# board.net
KiCad netlist of a schematic drawn in EAGLE
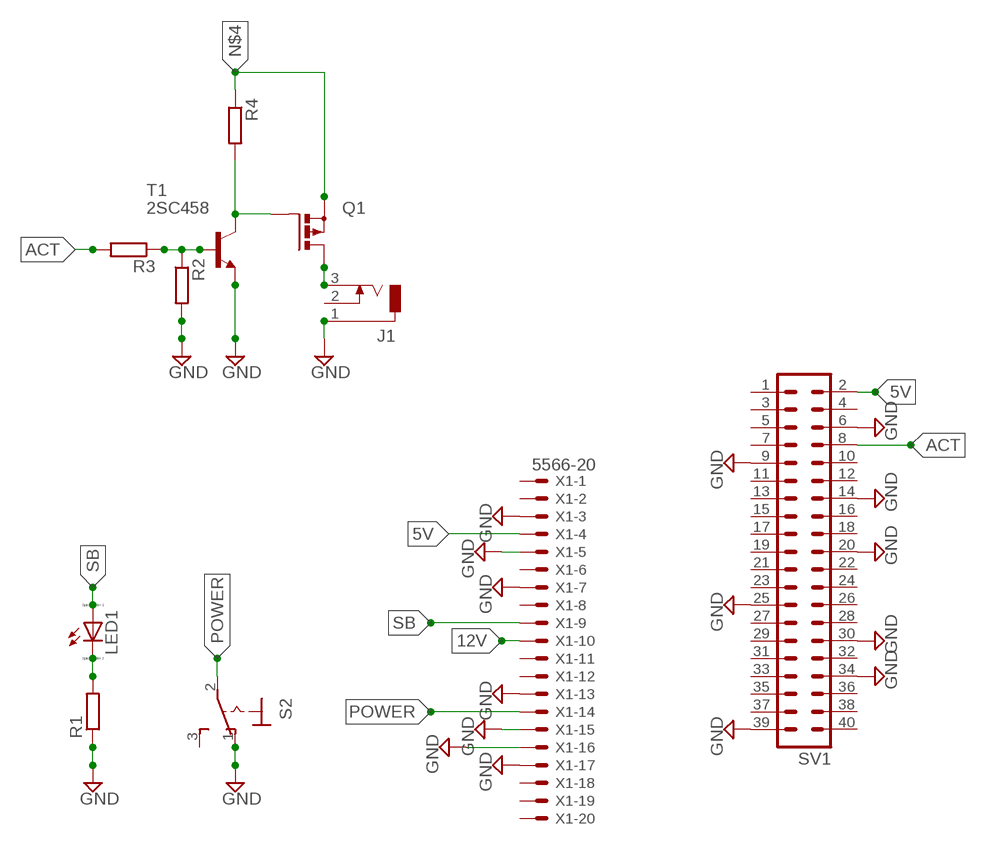
[diagram p0: schematic, sheet 1]

(export (version "E")
  (design (tool "Eeschema 10.0.6"))
  (components
    (comp (ref "J1")
      (value "DCJ0303")
      (footprint "eagle-import:DCJ0303")
      (libsource (lib "eagle-import") (part "DCJ0303"))
    )
    (comp (ref "LED1")
      (value "LED_ELD260")
      (footprint "eagle-import:LED_LD260")
      (libsource (lib "eagle-import") (part "LED_ELD260"))
    )
    (comp (ref "Q1")
      (value "PMOSFET_PTO220BV")
      (footprint "eagle-import:TO220BV")
      (libsource (lib "eagle-import") (part "PMOSFET_PTO220BV"))
    )
    (comp (ref "R1")
      (value "R-EU_0309/10")
      (footprint "eagle-import:0309_10")
      (libsource (lib "eagle-import") (part "R-EU_0309/10"))
    )
    (comp (ref "R2")
      (value "R-EU_0309/10")
      (footprint "eagle-import:0309_10")
      (libsource (lib "eagle-import") (part "R-EU_0309/10"))
    )
    (comp (ref "R3")
      (value "R-EU_0309/10")
      (footprint "eagle-import:0309_10")
      (libsource (lib "eagle-import") (part "R-EU_0309/10"))
    )
    (comp (ref "R4")
      (value "R-EU_0309/10")
      (footprint "eagle-import:0309_10")
      (libsource (lib "eagle-import") (part "R-EU_0309/10"))
    )
    (comp (ref "S2")
      (value "320-916")
      (footprint "eagle-import:320-916")
      (libsource (lib "eagle-import") (part "320-916"))
    )
    (comp (ref "SV1")
      (value "MA20-2")
      (footprint "eagle-import:MA20-2")
      (libsource (lib "eagle-import") (part "MA20-2"))
    )
    (comp (ref "T1")
      (value "2SC458")
      (footprint "eagle-import:TO92-ECB")
      (libsource (lib "eagle-import") (part "2SC458"))
    )
    (comp (ref "X1")
      (value "5566-20")
      (footprint "eagle-import:5566-20")
      (libsource (lib "eagle-import") (part "5566-20"))
    )
  )
  (nets
    (net (code "1") (name "5V") (class "Default")
      (node (ref "SV1") (pin "2") (pinfunction "2_2") (pintype "passive"))
      (node (ref "X1") (pin "4") (pinfunction "S_4") (pintype "passive"))
    )
    (net (code "2") (name "12V") (class "Default")
      (node (ref "X1") (pin "10") (pinfunction "S_10") (pintype "passive"))
    )
    (net (code "3") (name "ACT") (class "Default")
      (node (ref "R3") (pin "2") (pinfunction "2_2") (pintype "passive"))
      (node (ref "SV1") (pin "8") (pinfunction "8_8") (pintype "passive"))
    )
    (net (code "4") (name "GND") (class "Default")
      (node (ref "J1") (pin "1") (pinfunction "1_1") (pintype "passive"))
      (node (ref "R1") (pin "1") (pinfunction "1_1") (pintype "passive"))
      (node (ref "R2") (pin "2") (pinfunction "2_2") (pintype "passive"))
      (node (ref "S2") (pin "1") (pinfunction "O_1") (pintype "passive"))
      (node (ref "SV1") (pin "14") (pinfunction "14_14") (pintype "passive"))
      (node (ref "SV1") (pin "20") (pinfunction "20_20") (pintype "passive"))
      (node (ref "SV1") (pin "25") (pinfunction "25_25") (pintype "passive"))
      (node (ref "SV1") (pin "30") (pinfunction "30_30") (pintype "passive"))
      (node (ref "SV1") (pin "34") (pinfunction "34_34") (pintype "passive"))
      (node (ref "SV1") (pin "39") (pinfunction "39_39") (pintype "passive"))
      (node (ref "SV1") (pin "6") (pinfunction "6_6") (pintype "passive"))
      (node (ref "SV1") (pin "9") (pinfunction "9_9") (pintype "passive"))
      (node (ref "T1") (pin "E") (pinfunction "E_E") (pintype "passive"))
      (node (ref "X1") (pin "13") (pinfunction "S_13") (pintype "passive"))
      (node (ref "X1") (pin "15") (pinfunction "S_15") (pintype "passive"))
      (node (ref "X1") (pin "16") (pinfunction "S_16") (pintype "passive"))
      (node (ref "X1") (pin "17") (pinfunction "S_17") (pintype "passive"))
      (node (ref "X1") (pin "3") (pinfunction "S_3") (pintype "passive"))
      (node (ref "X1") (pin "5") (pinfunction "S_5") (pintype "passive"))
      (node (ref "X1") (pin "7") (pinfunction "S_7") (pintype "passive"))
    )
    (net (code "5") (name "N$4") (class "Default")
      (node (ref "Q1") (pin "S") (pinfunction "S_S") (pintype "passive"))
      (node (ref "R4") (pin "1") (pinfunction "1_1") (pintype "passive"))
    )
    (net (code "6") (name "Net-(J1-Pad3)") (class "Default")
      (node (ref "J1") (pin "3") (pinfunction "3_3") (pintype "passive"))
      (node (ref "Q1") (pin "D") (pinfunction "D_D") (pintype "passive"))
    )
    (net (code "7") (name "Net-(LED1-C)") (class "Default")
      (node (ref "LED1") (pin "K") (pinfunction "C_K") (pintype "passive"))
      (node (ref "R1") (pin "2") (pinfunction "2_2") (pintype "passive"))
    )
    (net (code "8") (name "Net-(Q1-PadG)") (class "Default")
      (node (ref "Q1") (pin "G") (pinfunction "G_G") (pintype "passive"))
      (node (ref "R4") (pin "2") (pinfunction "2_2") (pintype "passive"))
      (node (ref "T1") (pin "C") (pinfunction "C_C") (pintype "passive"))
    )
    (net (code "9") (name "Net-(R2-Pad1)") (class "Default")
      (node (ref "R2") (pin "1") (pinfunction "1_1") (pintype "passive"))
      (node (ref "R3") (pin "1") (pinfunction "1_1") (pintype "passive"))
      (node (ref "T1") (pin "B") (pinfunction "B_B") (pintype "passive"))
    )
    (net (code "10") (name "POWER") (class "Default")
      (node (ref "S2") (pin "2") (pinfunction "P_2") (pintype "passive"))
      (node (ref "X1") (pin "14") (pinfunction "S_14") (pintype "passive"))
    )
    (net (code "11") (name "SB") (class "Default")
      (node (ref "LED1") (pin "A") (pinfunction "A_A") (pintype "passive"))
      (node (ref "X1") (pin "9") (pinfunction "S_9") (pintype "passive"))
    )
    (net (code "12") (name "unconnected-(J1-Pad2)") (class "Default")
      (node (ref "J1") (pin "2") (pinfunction "2_2") (pintype "passive"))
    )
    (net (code "13") (name "unconnected-(S2-S-Pad3)") (class "Default")
      (node (ref "S2") (pin "3") (pinfunction "S_3") (pintype "passive"))
    )
    (net (code "14") (name "unconnected-(SV1-Pad1)") (class "Default")
      (node (ref "SV1") (pin "1") (pinfunction "1_1") (pintype "passive"))
    )
    (net (code "15") (name "unconnected-(SV1-Pad3)") (class "Default")
      (node (ref "SV1") (pin "3") (pinfunction "3_3") (pintype "passive"))
    )
    (net (code "16") (name "unconnected-(SV1-Pad4)") (class "Default")
      (node (ref "SV1") (pin "4") (pinfunction "4_4") (pintype "passive"))
    )
    (net (code "17") (name "unconnected-(SV1-Pad5)") (class "Default")
      (node (ref "SV1") (pin "5") (pinfunction "5_5") (pintype "passive"))
    )
    (net (code "18") (name "unconnected-(SV1-Pad7)") (class "Default")
      (node (ref "SV1") (pin "7") (pinfunction "7_7") (pintype "passive"))
    )
    (net (code "19") (name "unconnected-(SV1-Pad10)") (class "Default")
      (node (ref "SV1") (pin "10") (pinfunction "10_10") (pintype "passive"))
    )
    (net (code "20") (name "unconnected-(SV1-Pad11)") (class "Default")
      (node (ref "SV1") (pin "11") (pinfunction "11_11") (pintype "passive"))
    )
    (net (code "21") (name "unconnected-(SV1-Pad12)") (class "Default")
      (node (ref "SV1") (pin "12") (pinfunction "12_12") (pintype "passive"))
    )
    (net (code "22") (name "unconnected-(SV1-Pad13)") (class "Default")
      (node (ref "SV1") (pin "13") (pinfunction "13_13") (pintype "passive"))
    )
    (net (code "23") (name "unconnected-(SV1-Pad15)") (class "Default")
      (node (ref "SV1") (pin "15") (pinfunction "15_15") (pintype "passive"))
    )
    (net (code "24") (name "unconnected-(SV1-Pad16)") (class "Default")
      (node (ref "SV1") (pin "16") (pinfunction "16_16") (pintype "passive"))
    )
    (net (code "25") (name "unconnected-(SV1-Pad17)") (class "Default")
      (node (ref "SV1") (pin "17") (pinfunction "17_17") (pintype "passive"))
    )
    (net (code "26") (name "unconnected-(SV1-Pad18)") (class "Default")
      (node (ref "SV1") (pin "18") (pinfunction "18_18") (pintype "passive"))
    )
    (net (code "27") (name "unconnected-(SV1-Pad19)") (class "Default")
      (node (ref "SV1") (pin "19") (pinfunction "19_19") (pintype "passive"))
    )
    (net (code "28") (name "unconnected-(SV1-Pad21)") (class "Default")
      (node (ref "SV1") (pin "21") (pinfunction "21_21") (pintype "passive"))
    )
    (net (code "29") (name "unconnected-(SV1-Pad22)") (class "Default")
      (node (ref "SV1") (pin "22") (pinfunction "22_22") (pintype "passive"))
    )
    (net (code "30") (name "unconnected-(SV1-Pad23)") (class "Default")
      (node (ref "SV1") (pin "23") (pinfunction "23_23") (pintype "passive"))
    )
    (net (code "31") (name "unconnected-(SV1-Pad24)") (class "Default")
      (node (ref "SV1") (pin "24") (pinfunction "24_24") (pintype "passive"))
    )
    (net (code "32") (name "unconnected-(SV1-Pad26)") (class "Default")
      (node (ref "SV1") (pin "26") (pinfunction "26_26") (pintype "passive"))
    )
    (net (code "33") (name "unconnected-(SV1-Pad27)") (class "Default")
      (node (ref "SV1") (pin "27") (pinfunction "27_27") (pintype "passive"))
    )
    (net (code "34") (name "unconnected-(SV1-Pad28)") (class "Default")
      (node (ref "SV1") (pin "28") (pinfunction "28_28") (pintype "passive"))
    )
    (net (code "35") (name "unconnected-(SV1-Pad29)") (class "Default")
      (node (ref "SV1") (pin "29") (pinfunction "29_29") (pintype "passive"))
    )
    (net (code "36") (name "unconnected-(SV1-Pad31)") (class "Default")
      (node (ref "SV1") (pin "31") (pinfunction "31_31") (pintype "passive"))
    )
    (net (code "37") (name "unconnected-(SV1-Pad32)") (class "Default")
      (node (ref "SV1") (pin "32") (pinfunction "32_32") (pintype "passive"))
    )
    (net (code "38") (name "unconnected-(SV1-Pad33)") (class "Default")
      (node (ref "SV1") (pin "33") (pinfunction "33_33") (pintype "passive"))
    )
    (net (code "39") (name "unconnected-(SV1-Pad35)") (class "Default")
      (node (ref "SV1") (pin "35") (pinfunction "35_35") (pintype "passive"))
    )
    (net (code "40") (name "unconnected-(SV1-Pad36)") (class "Default")
      (node (ref "SV1") (pin "36") (pinfunction "36_36") (pintype "passive"))
    )
    (net (code "41") (name "unconnected-(SV1-Pad37)") (class "Default")
      (node (ref "SV1") (pin "37") (pinfunction "37_37") (pintype "passive"))
    )
    (net (code "42") (name "unconnected-(SV1-Pad38)") (class "Default")
      (node (ref "SV1") (pin "38") (pinfunction "38_38") (pintype "passive"))
    )
    (net (code "43") (name "unconnected-(SV1-Pad40)") (class "Default")
      (node (ref "SV1") (pin "40") (pinfunction "40_40") (pintype "passive"))
    )
    (net (code "44") (name "unconnected-(X1A-S-Pad1)") (class "Default")
      (node (ref "X1") (pin "1") (pinfunction "S_1") (pintype "passive"))
    )
    (net (code "45") (name "unconnected-(X1C-S-Pad11)") (class "Default")
      (node (ref "X1") (pin "11") (pinfunction "S_11") (pintype "passive"))
    )
    (net (code "46") (name "unconnected-(X1D-S-Pad12)") (class "Default")
      (node (ref "X1") (pin "12") (pinfunction "S_12") (pintype "passive"))
    )
    (net (code "47") (name "unconnected-(X1J-S-Pad18)") (class "Default")
      (node (ref "X1") (pin "18") (pinfunction "S_18") (pintype "passive"))
    )
    (net (code "48") (name "unconnected-(X1K-S-Pad19)") (class "Default")
      (node (ref "X1") (pin "19") (pinfunction "S_19") (pintype "passive"))
    )
    (net (code "49") (name "unconnected-(X1L-S-Pad2)") (class "Default")
      (node (ref "X1") (pin "2") (pinfunction "S_2") (pintype "passive"))
    )
    (net (code "50") (name "unconnected-(X1M-S-Pad20)") (class "Default")
      (node (ref "X1") (pin "20") (pinfunction "S_20") (pintype "passive"))
    )
    (net (code "51") (name "unconnected-(X1Q-S-Pad6)") (class "Default")
      (node (ref "X1") (pin "6") (pinfunction "S_6") (pintype "passive"))
    )
    (net (code "52") (name "unconnected-(X1S-S-Pad8)") (class "Default")
      (node (ref "X1") (pin "8") (pinfunction "S_8") (pintype "passive"))
    )
  )
)
